# nes-programmer-1.net
KiCad netlist of a schematic drawn in EAGLE
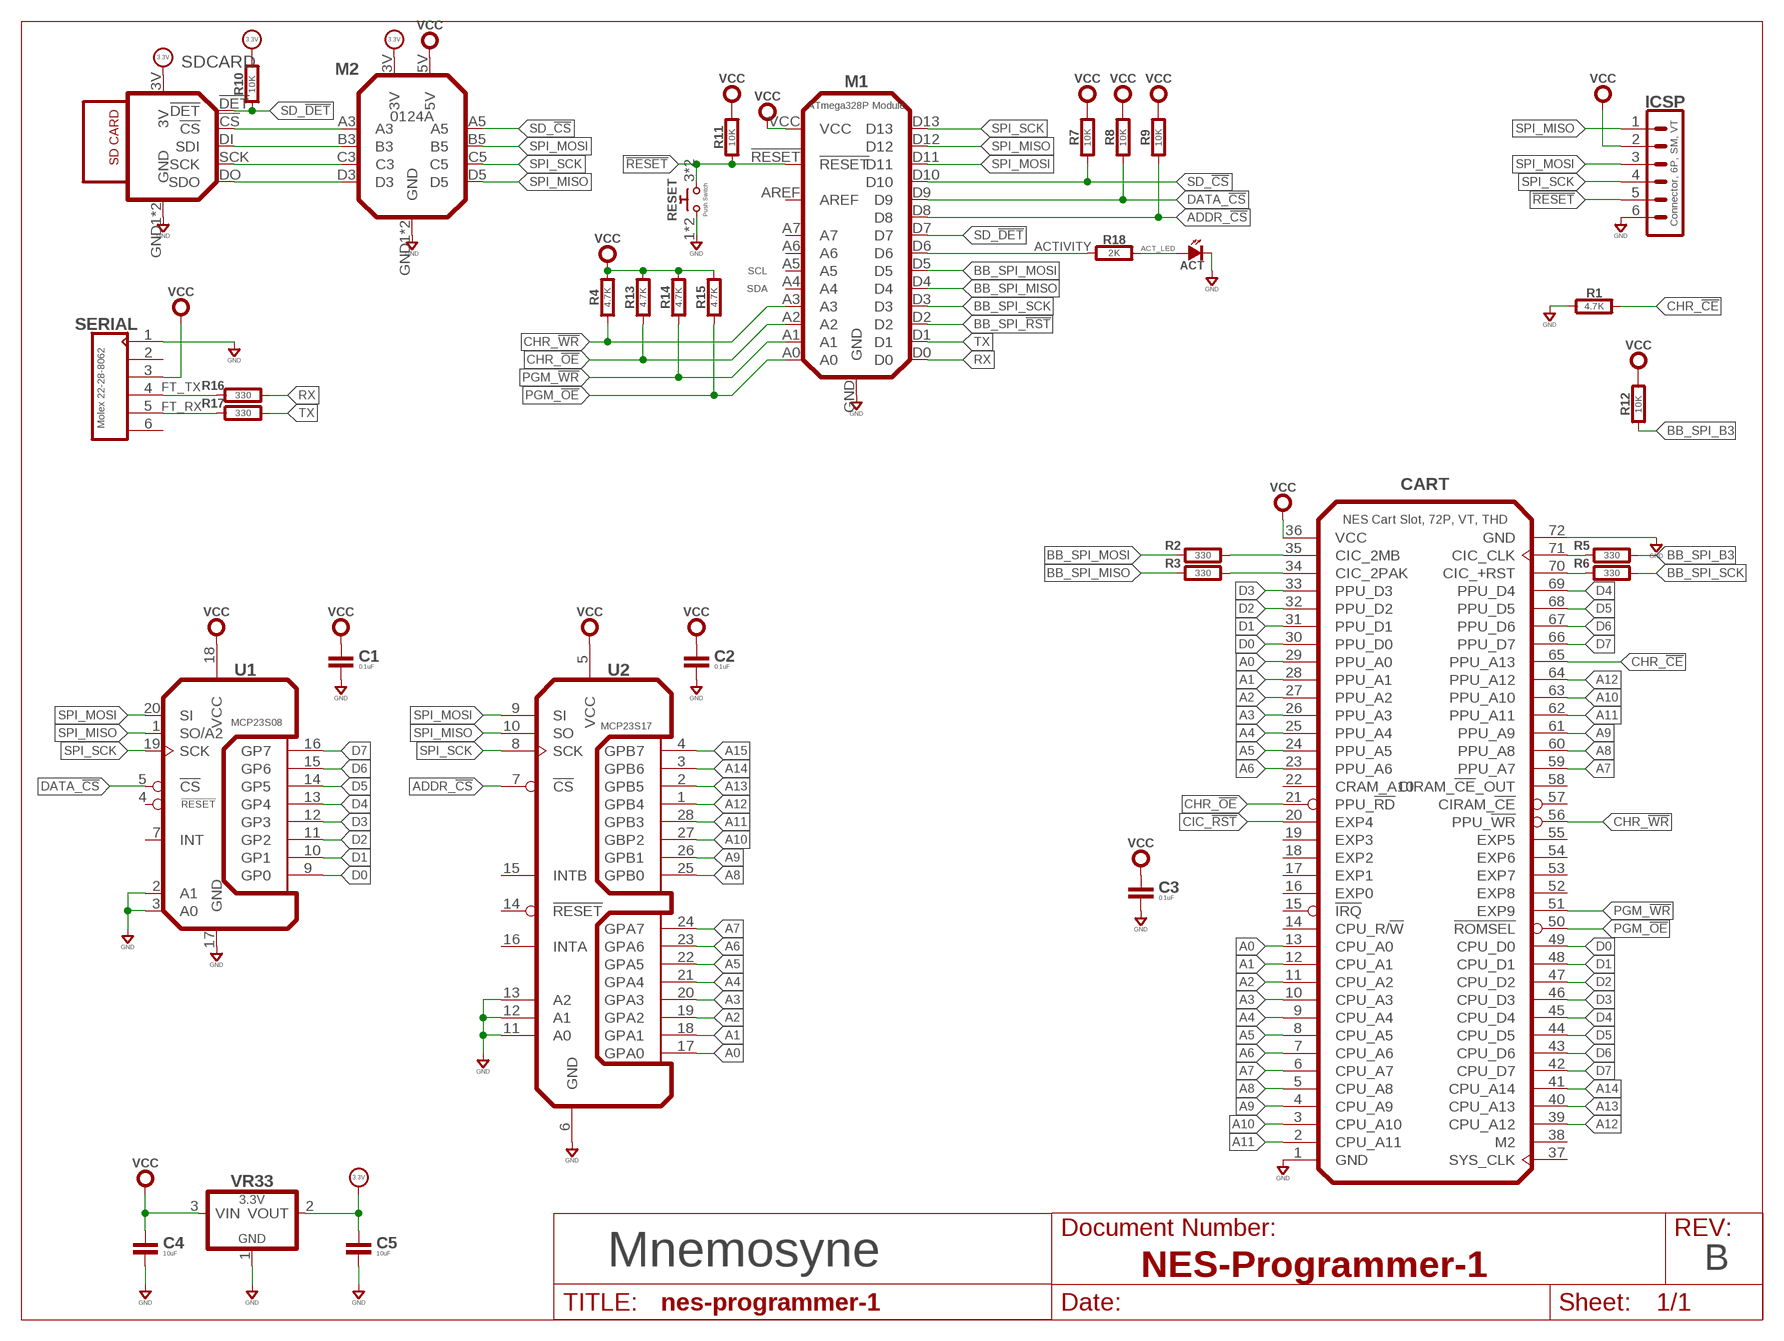
[diagram p0: schematic, sheet 1]

(export (version "E")
  (design (tool "Eeschema 10.0.6"))
  (components
    (comp (ref "ACT")
      (value "SMT0603")
      (footprint "eagle-import:SMD_0603")
      (libsource (lib "eagle-import") (part "SMT0603"))
    )
    (comp (ref "C1")
      (value "0.1uF")
      (footprint "eagle-import:0603-CAP")
      (libsource (lib "eagle-import") (part "CAPACITOR0603"))
    )
    (comp (ref "C2")
      (value "0.1uF")
      (footprint "eagle-import:0603-CAP")
      (libsource (lib "eagle-import") (part "CAPACITOR0603"))
    )
    (comp (ref "C3")
      (value "0.1uF")
      (footprint "eagle-import:0603-CAP")
      (libsource (lib "eagle-import") (part "CAPACITOR0603"))
    )
    (comp (ref "C4")
      (value "10uF")
      (footprint "eagle-import:0603-CAP")
      (libsource (lib "eagle-import") (part "CAPACITOR0603"))
    )
    (comp (ref "C5")
      (value "10uF")
      (footprint "eagle-import:0603-CAP")
      (libsource (lib "eagle-import") (part "CAPACITOR0603"))
    )
    (comp (ref "CART")
      (value "NES Cart Slot, 72P, VT, THD")
      (footprint "eagle-import:NES-CONNECTOR-VT-THD")
      (fields (field (name "MFR") "AliExpress") (field (name "MPN") "not defined"))
      (libsource (lib "eagle-import") (part "NES-RECEPTACLE-VT-THD"))
    )
    (comp (ref "ICSP")
      (value "Connector, 6P, SM, VT")
      (footprint "eagle-import:BM06B-SRSS-TB")
      (fields (field (name "MFR") "JST") (field (name "MPN") "BM06-SRSS-TB"))
      (libsource (lib "eagle-import") (part "06P-SM-VT-SMT"))
    )
    (comp (ref "M1")
      (value "ATmega328P Module")
      (footprint "eagle-import:0119A")
      (fields (field (name "MFR") "Circuit Monkey") (field (name "MPN") "0119A"))
      (libsource (lib "eagle-import") (part "0119REV-A"))
    )
    (comp (ref "M2")
      (value "0124A")
      (footprint "eagle-import:0124A")
      (fields (field (name "MFR") "Circuit Monkey"))
      (libsource (lib "eagle-import") (part "0124REV-A"))
    )
    (comp (ref "R1")
      (value "4.7K")
      (footprint "eagle-import:0603-RES")
      (libsource (lib "eagle-import") (part "RESISTOR0603"))
    )
    (comp (ref "R2")
      (value "330")
      (footprint "eagle-import:0603-RES")
      (libsource (lib "eagle-import") (part "RESISTOR0603"))
    )
    (comp (ref "R3")
      (value "330")
      (footprint "eagle-import:0603-RES")
      (libsource (lib "eagle-import") (part "RESISTOR0603"))
    )
    (comp (ref "R4")
      (value "4.7K")
      (footprint "eagle-import:0603-RES")
      (libsource (lib "eagle-import") (part "RESISTOR0603"))
    )
    (comp (ref "R5")
      (value "330")
      (footprint "eagle-import:0603-RES")
      (libsource (lib "eagle-import") (part "RESISTOR0603"))
    )
    (comp (ref "R6")
      (value "330")
      (footprint "eagle-import:0603-RES")
      (libsource (lib "eagle-import") (part "RESISTOR0603"))
    )
    (comp (ref "R7")
      (value "10K")
      (footprint "eagle-import:0603-RES")
      (libsource (lib "eagle-import") (part "RESISTOR0603"))
    )
    (comp (ref "R8")
      (value "10K")
      (footprint "eagle-import:0603-RES")
      (libsource (lib "eagle-import") (part "RESISTOR0603"))
    )
    (comp (ref "R9")
      (value "10K")
      (footprint "eagle-import:0603-RES")
      (libsource (lib "eagle-import") (part "RESISTOR0603"))
    )
    (comp (ref "R10")
      (value "10K")
      (footprint "eagle-import:0603-RES")
      (libsource (lib "eagle-import") (part "RESISTOR0603"))
    )
    (comp (ref "R11")
      (value "10K")
      (footprint "eagle-import:0603-RES")
      (libsource (lib "eagle-import") (part "RESISTOR0603"))
    )
    (comp (ref "R12")
      (value "10K")
      (footprint "eagle-import:0603-RES")
      (libsource (lib "eagle-import") (part "RESISTOR0603"))
    )
    (comp (ref "R13")
      (value "4.7K")
      (footprint "eagle-import:0603-RES")
      (libsource (lib "eagle-import") (part "RESISTOR0603"))
    )
    (comp (ref "R14")
      (value "4.7K")
      (footprint "eagle-import:0603-RES")
      (libsource (lib "eagle-import") (part "RESISTOR0603"))
    )
    (comp (ref "R15")
      (value "4.7K")
      (footprint "eagle-import:0603-RES")
      (libsource (lib "eagle-import") (part "RESISTOR0603"))
    )
    (comp (ref "R16")
      (value "330")
      (footprint "eagle-import:0603-RES")
      (libsource (lib "eagle-import") (part "RESISTOR0603"))
    )
    (comp (ref "R17")
      (value "330")
      (footprint "eagle-import:0603-RES")
      (libsource (lib "eagle-import") (part "RESISTOR0603"))
    )
    (comp (ref "R18")
      (value "2K")
      (footprint "eagle-import:0603-RES")
      (libsource (lib "eagle-import") (part "RESISTOR0603"))
    )
    (comp (ref "RESET")
      (value "Push Switch")
      (footprint "eagle-import:B3SN")
      (fields (field (name "MFR") "Omron") (field (name "MPN") "B3SN"))
      (libsource (lib "eagle-import") (part "PUSHBTN-MOMB3SN"))
    )
    (comp (ref "SDCARD")
      (value "0127REV-A")
      (footprint "eagle-import:0127A")
      (fields (field (name "MFR") "Circuit Monkey") (field (name "MPN") "0127"))
      (libsource (lib "eagle-import") (part "0127REV-A"))
    )
    (comp (ref "SERIAL")
      (value "Molex 22-28-8062")
      (footprint "eagle-import:MA06X1-RA-THD")
      (libsource (lib "eagle-import") (part "CON_06X1-RA"))
    )
    (comp (ref "U1")
      (value "MCP23S08")
      (footprint "eagle-import:QFN-20")
      (fields (field (name "MFR") "Microchip") (field (name "MPN") "MCP23S08-E/ML"))
      (libsource (lib "eagle-import") (part "MCP23S08-QFN"))
    )
    (comp (ref "U2")
      (value "MCP23S17")
      (footprint "eagle-import:QFN-28-6X6")
      (fields (field (name "MFR") "Microchip") (field (name "MPN") "MCP23S17-x/ML"))
      (libsource (lib "eagle-import") (part "MCP23S17-QFN"))
    )
    (comp (ref "VR33")
      (value "3.3V")
      (footprint "eagle-import:SOT-23")
      (fields (field (name "MPN") "AP2120N-3.3"))
      (libsource (lib "eagle-import") (part "LDO-3P--3.3V-SOT23"))
    )
  )
  (nets
    (net (code "1") (name "/ACTIVITY") (class "Default")
      (node (ref "M1") (pin "D6") (pinfunction "D6_D6") (pintype "bidirectional"))
      (node (ref "R18") (pin "1") (pinfunction "1_1") (pintype "passive"))
    )
    (net (code "2") (name "/ACT_LED") (class "Default")
      (node (ref "ACT") (pin "A") (pinfunction "A_A") (pintype "passive"))
      (node (ref "R18") (pin "2") (pinfunction "2_2") (pintype "passive"))
    )
    (net (code "3") (name "/ADDR_~{CS}") (class "Default")
      (node (ref "M1") (pin "D8") (pinfunction "D8_D8") (pintype "bidirectional"))
      (node (ref "R9") (pin "1") (pinfunction "1_1") (pintype "passive"))
      (node (ref "U2") (pin "7") (pinfunction "~{CS}_7") (pintype "input"))
    )
    (net (code "4") (name "/BB_SPI_~{RST}") (class "Default")
      (node (ref "M1") (pin "D2") (pinfunction "D2_D2") (pintype "bidirectional"))
    )
    (net (code "5") (name "/CHR_~{CE}") (class "Default")
      (node (ref "CART") (pin "65") (pinfunction "PPU_A13_65") (pintype "input"))
      (node (ref "R1") (pin "2") (pinfunction "2_2") (pintype "passive"))
    )
    (net (code "6") (name "/CHR_~{OE}") (class "Default")
      (node (ref "CART") (pin "21") (pinfunction "PPU_~{RD}_21") (pintype "input"))
      (node (ref "M1") (pin "A2") (pinfunction "A2_A2") (pintype "bidirectional"))
      (node (ref "R13") (pin "1") (pinfunction "1_1") (pintype "passive"))
    )
    (net (code "7") (name "/CHR_~{WR}") (class "Default")
      (node (ref "CART") (pin "56") (pinfunction "PPU_~{WR}_56") (pintype "input"))
      (node (ref "M1") (pin "A3") (pinfunction "A3_A3") (pintype "bidirectional"))
      (node (ref "R4") (pin "1") (pinfunction "1_1") (pintype "passive"))
    )
    (net (code "8") (name "/CIC_~{RST}") (class "Default")
      (node (ref "CART") (pin "20") (pinfunction "EXP4_20") (pintype "bidirectional"))
    )
    (net (code "9") (name "/DATA_~{CS}") (class "Default")
      (node (ref "M1") (pin "D9") (pinfunction "D9_D9") (pintype "bidirectional"))
      (node (ref "R8") (pin "1") (pinfunction "1_1") (pintype "passive"))
      (node (ref "U1") (pin "5") (pinfunction "~{CS}_5") (pintype "input"))
    )
    (net (code "10") (name "/FT_RX") (class "Default")
      (node (ref "R17") (pin "1") (pinfunction "1_1") (pintype "passive"))
      (node (ref "SERIAL") (pin "5") (pinfunction "5_5") (pintype "passive"))
    )
    (net (code "11") (name "/FT_TX") (class "Default")
      (node (ref "R16") (pin "1") (pinfunction "1_1") (pintype "passive"))
      (node (ref "SERIAL") (pin "4") (pinfunction "4_4") (pintype "passive"))
    )
    (net (code "12") (name "/PGM_~{OE}") (class "Default")
      (node (ref "CART") (pin "50") (pinfunction "~{ROMSEL}_50") (pintype "input"))
      (node (ref "M1") (pin "A0") (pinfunction "A0_A0") (pintype "bidirectional"))
      (node (ref "R15") (pin "1") (pinfunction "1_1") (pintype "passive"))
    )
    (net (code "13") (name "/PGM_~{WR}") (class "Default")
      (node (ref "CART") (pin "51") (pinfunction "EXP9_51") (pintype "bidirectional"))
      (node (ref "M1") (pin "A1") (pinfunction "A1_A1") (pintype "bidirectional"))
      (node (ref "R14") (pin "1") (pinfunction "1_1") (pintype "passive"))
    )
    (net (code "14") (name "/SD_~{CS}") (class "Default")
      (node (ref "M1") (pin "D10") (pinfunction "D10_D10") (pintype "bidirectional"))
      (node (ref "M2") (pin "A5") (pinfunction "A5_A5") (pintype "bidirectional"))
      (node (ref "R7") (pin "1") (pinfunction "1_1") (pintype "passive"))
    )
    (net (code "15") (name "/SD_~{DET}") (class "Default")
      (node (ref "M1") (pin "D7") (pinfunction "D7_D7") (pintype "bidirectional"))
      (node (ref "R10") (pin "1") (pinfunction "1_1") (pintype "passive"))
      (node (ref "SDCARD") (pin "!DET") (pinfunction "~{DET}_!DET") (pintype "bidirectional"))
    )
    (net (code "16") (name "/~{RESET}") (class "Default")
      (node (ref "ICSP") (pin "5") (pinfunction "5_5") (pintype "passive"))
      (node (ref "M1") (pin "!RESET") (pinfunction "~{RESET}_!RESET") (pintype "bidirectional"))
      (node (ref "R11") (pin "1") (pinfunction "1_1") (pintype "passive"))
      (node (ref "RESET") (pin "3") (pinfunction "2_3") (pintype "passive"))
      (node (ref "RESET") (pin "4") (pinfunction "2_4") (pintype "passive"))
    )
    (net (code "17") (name "3.3V") (class "Default")
      (node (ref "C5") (pin "1") (pinfunction "1_1") (pintype "passive"))
      (node (ref "M2") (pin "3V") (pinfunction "3V_3V") (pintype "bidirectional"))
      (node (ref "R10") (pin "2") (pinfunction "2_2") (pintype "passive"))
      (node (ref "SDCARD") (pin "3V") (pinfunction "3V_3V") (pintype "bidirectional"))
      (node (ref "VR33") (pin "2") (pinfunction "VOUT_2") (pintype "power_in"))
    )
    (net (code "18") (name "A0") (class "Default")
      (node (ref "CART") (pin "13") (pinfunction "CPU_A0_13") (pintype "input"))
      (node (ref "CART") (pin "29") (pinfunction "PPU_A0_29") (pintype "input"))
      (node (ref "U2") (pin "17") (pinfunction "GPA0_17") (pintype "bidirectional"))
    )
    (net (code "19") (name "A1") (class "Default")
      (node (ref "CART") (pin "12") (pinfunction "CPU_A1_12") (pintype "input"))
      (node (ref "CART") (pin "28") (pinfunction "PPU_A1_28") (pintype "input"))
      (node (ref "U2") (pin "18") (pinfunction "GPA1_18") (pintype "bidirectional"))
    )
    (net (code "20") (name "A2") (class "Default")
      (node (ref "CART") (pin "11") (pinfunction "CPU_A2_11") (pintype "input"))
      (node (ref "CART") (pin "27") (pinfunction "PPU_A2_27") (pintype "input"))
      (node (ref "U2") (pin "19") (pinfunction "GPA2_19") (pintype "bidirectional"))
    )
    (net (code "21") (name "A3") (class "Default")
      (node (ref "CART") (pin "10") (pinfunction "CPU_A3_10") (pintype "input"))
      (node (ref "CART") (pin "26") (pinfunction "PPU_A3_26") (pintype "input"))
      (node (ref "U2") (pin "20") (pinfunction "GPA3_20") (pintype "bidirectional"))
    )
    (net (code "22") (name "A4") (class "Default")
      (node (ref "CART") (pin "25") (pinfunction "PPU_A4_25") (pintype "input"))
      (node (ref "CART") (pin "9") (pinfunction "CPU_A4_9") (pintype "input"))
      (node (ref "U2") (pin "21") (pinfunction "GPA4_21") (pintype "bidirectional"))
    )
    (net (code "23") (name "A5") (class "Default")
      (node (ref "CART") (pin "24") (pinfunction "PPU_A5_24") (pintype "input"))
      (node (ref "CART") (pin "8") (pinfunction "CPU_A5_8") (pintype "input"))
      (node (ref "U2") (pin "22") (pinfunction "GPA5_22") (pintype "bidirectional"))
    )
    (net (code "24") (name "A6") (class "Default")
      (node (ref "CART") (pin "23") (pinfunction "PPU_A6_23") (pintype "input"))
      (node (ref "CART") (pin "7") (pinfunction "CPU_A6_7") (pintype "input"))
      (node (ref "U2") (pin "23") (pinfunction "GPA6_23") (pintype "bidirectional"))
    )
    (net (code "25") (name "A7") (class "Default")
      (node (ref "CART") (pin "59") (pinfunction "PPU_A7_59") (pintype "input"))
      (node (ref "CART") (pin "6") (pinfunction "CPU_A7_6") (pintype "input"))
      (node (ref "U2") (pin "24") (pinfunction "GPA7_24") (pintype "bidirectional"))
    )
    (net (code "26") (name "A8") (class "Default")
      (node (ref "CART") (pin "5") (pinfunction "CPU_A8_5") (pintype "input"))
      (node (ref "CART") (pin "60") (pinfunction "PPU_A8_60") (pintype "input"))
      (node (ref "U2") (pin "25") (pinfunction "GPB0_25") (pintype "bidirectional"))
    )
    (net (code "27") (name "A9") (class "Default")
      (node (ref "CART") (pin "4") (pinfunction "CPU_A9_4") (pintype "input"))
      (node (ref "CART") (pin "61") (pinfunction "PPU_A9_61") (pintype "input"))
      (node (ref "U2") (pin "26") (pinfunction "GPB1_26") (pintype "bidirectional"))
    )
    (net (code "28") (name "A10") (class "Default")
      (node (ref "CART") (pin "3") (pinfunction "CPU_A10_3") (pintype "input"))
      (node (ref "CART") (pin "63") (pinfunction "PPU_A10_63") (pintype "input"))
      (node (ref "U2") (pin "27") (pinfunction "GBP2_27") (pintype "bidirectional"))
    )
    (net (code "29") (name "A11") (class "Default")
      (node (ref "CART") (pin "2") (pinfunction "CPU_A11_2") (pintype "input"))
      (node (ref "CART") (pin "62") (pinfunction "PPU_A11_62") (pintype "input"))
      (node (ref "U2") (pin "28") (pinfunction "GPB3_28") (pintype "bidirectional"))
    )
    (net (code "30") (name "A12") (class "Default")
      (node (ref "CART") (pin "39") (pinfunction "CPU_A12_39") (pintype "input"))
      (node (ref "CART") (pin "64") (pinfunction "PPU_A12_64") (pintype "input"))
      (node (ref "U2") (pin "1") (pinfunction "GPB4_1") (pintype "bidirectional"))
    )
    (net (code "31") (name "A13") (class "Default")
      (node (ref "CART") (pin "40") (pinfunction "CPU_A13_40") (pintype "input"))
      (node (ref "U2") (pin "2") (pinfunction "GPB5_2") (pintype "bidirectional"))
    )
    (net (code "32") (name "A14") (class "Default")
      (node (ref "CART") (pin "41") (pinfunction "CPU_A14_41") (pintype "input"))
      (node (ref "U2") (pin "3") (pinfunction "GPB6_3") (pintype "bidirectional"))
    )
    (net (code "33") (name "A15") (class "Default")
      (node (ref "U2") (pin "4") (pinfunction "GPB7_4") (pintype "bidirectional"))
    )
    (net (code "34") (name "BB_SPI_B3") (class "Default")
      (node (ref "R12") (pin "1") (pinfunction "1_1") (pintype "passive"))
      (node (ref "R5") (pin "2") (pinfunction "2_2") (pintype "passive"))
    )
    (net (code "35") (name "BB_SPI_MISO") (class "Default")
      (node (ref "M1") (pin "D4") (pinfunction "D4_D4") (pintype "bidirectional"))
      (node (ref "R3") (pin "1") (pinfunction "1_1") (pintype "passive"))
    )
    (net (code "36") (name "BB_SPI_MOSI") (class "Default")
      (node (ref "M1") (pin "D5") (pinfunction "D5_D5") (pintype "bidirectional"))
      (node (ref "R2") (pin "1") (pinfunction "1_1") (pintype "passive"))
    )
    (net (code "37") (name "BB_SPI_SCK") (class "Default")
      (node (ref "M1") (pin "D3") (pinfunction "D3_D3") (pintype "bidirectional"))
      (node (ref "R6") (pin "2") (pinfunction "2_2") (pintype "passive"))
    )
    (net (code "38") (name "D0") (class "Default")
      (node (ref "CART") (pin "30") (pinfunction "PPU_D0_30") (pintype "bidirectional"))
      (node (ref "CART") (pin "49") (pinfunction "CPU_D0_49") (pintype "bidirectional"))
      (node (ref "U1") (pin "9") (pinfunction "GP0_9") (pintype "bidirectional"))
    )
    (net (code "39") (name "D1") (class "Default")
      (node (ref "CART") (pin "31") (pinfunction "PPU_D1_31") (pintype "bidirectional"))
      (node (ref "CART") (pin "48") (pinfunction "CPU_D1_48") (pintype "bidirectional"))
      (node (ref "U1") (pin "10") (pinfunction "GP1_10") (pintype "bidirectional"))
    )
    (net (code "40") (name "D2") (class "Default")
      (node (ref "CART") (pin "32") (pinfunction "PPU_D2_32") (pintype "bidirectional"))
      (node (ref "CART") (pin "47") (pinfunction "CPU_D2_47") (pintype "bidirectional"))
      (node (ref "U1") (pin "11") (pinfunction "GP2_11") (pintype "bidirectional"))
    )
    (net (code "41") (name "D3") (class "Default")
      (node (ref "CART") (pin "33") (pinfunction "PPU_D3_33") (pintype "bidirectional"))
      (node (ref "CART") (pin "46") (pinfunction "CPU_D3_46") (pintype "bidirectional"))
      (node (ref "U1") (pin "12") (pinfunction "GP3_12") (pintype "bidirectional"))
    )
    (net (code "42") (name "D4") (class "Default")
      (node (ref "CART") (pin "45") (pinfunction "CPU_D4_45") (pintype "bidirectional"))
      (node (ref "CART") (pin "69") (pinfunction "PPU_D4_69") (pintype "bidirectional"))
      (node (ref "U1") (pin "13") (pinfunction "GP4_13") (pintype "bidirectional"))
    )
    (net (code "43") (name "D5") (class "Default")
      (node (ref "CART") (pin "44") (pinfunction "CPU_D5_44") (pintype "bidirectional"))
      (node (ref "CART") (pin "68") (pinfunction "PPU_D5_68") (pintype "bidirectional"))
      (node (ref "U1") (pin "14") (pinfunction "GP5_14") (pintype "bidirectional"))
    )
    (net (code "44") (name "D6") (class "Default")
      (node (ref "CART") (pin "43") (pinfunction "CPU_D6_43") (pintype "bidirectional"))
      (node (ref "CART") (pin "67") (pinfunction "PPU_D6_67") (pintype "bidirectional"))
      (node (ref "U1") (pin "15") (pinfunction "GP6_15") (pintype "bidirectional"))
    )
    (net (code "45") (name "D7") (class "Default")
      (node (ref "CART") (pin "42") (pinfunction "CPU_D7_42") (pintype "bidirectional"))
      (node (ref "CART") (pin "66") (pinfunction "PPU_D7_66") (pintype "bidirectional"))
      (node (ref "U1") (pin "16") (pinfunction "GP7_16") (pintype "bidirectional"))
    )
    (net (code "46") (name "GND") (class "Default")
      (node (ref "ACT") (pin "K") (pinfunction "C_K") (pintype "passive"))
      (node (ref "C1") (pin "2") (pinfunction "2_2") (pintype "passive"))
      (node (ref "C2") (pin "2") (pinfunction "2_2") (pintype "passive"))
      (node (ref "C3") (pin "2") (pinfunction "2_2") (pintype "passive"))
      (node (ref "C4") (pin "2") (pinfunction "2_2") (pintype "passive"))
      (node (ref "C5") (pin "2") (pinfunction "2_2") (pintype "passive"))
      (node (ref "CART") (pin "1") (pinfunction "GND_1") (pintype "power_in"))
      (node (ref "CART") (pin "72") (pinfunction "GND_72") (pintype "bidirectional"))
      (node (ref "ICSP") (pin "6") (pinfunction "6_6") (pintype "passive"))
      (node (ref "M1") (pin "GND") (pinfunction "GND_GND") (pintype "bidirectional"))
      (node (ref "M2") (pin "GND1") (pinfunction "GND_GND1") (pintype "bidirectional"))
      (node (ref "M2") (pin "GND2") (pinfunction "GND_GND2") (pintype "bidirectional"))
      (node (ref "R1") (pin "1") (pinfunction "1_1") (pintype "passive"))
      (node (ref "RESET") (pin "1") (pinfunction "1_1") (pintype "passive"))
      (node (ref "RESET") (pin "2") (pinfunction "1_2") (pintype "passive"))
      (node (ref "SDCARD") (pin "GND1") (pinfunction "GND_GND1") (pintype "bidirectional"))
      (node (ref "SDCARD") (pin "GND2") (pinfunction "GND_GND2") (pintype "bidirectional"))
      (node (ref "SERIAL") (pin "1") (pinfunction "1_1") (pintype "passive"))
      (node (ref "U1") (pin "17") (pinfunction "GND_17") (pintype "power_in"))
      (node (ref "U1") (pin "2") (pinfunction "A1_2") (pintype "input"))
      (node (ref "U1") (pin "3") (pinfunction "A0_3") (pintype "input"))
      (node (ref "U2") (pin "11") (pinfunction "A0_11") (pintype "input"))
      (node (ref "U2") (pin "12") (pinfunction "A1_12") (pintype "input"))
      (node (ref "U2") (pin "13") (pinfunction "A2_13") (pintype "input"))
      (node (ref "U2") (pin "6") (pinfunction "GND_6") (pintype "power_in"))
      (node (ref "VR33") (pin "1") (pinfunction "GND_1") (pintype "power_in"))
    )
    (net (code "47") (name "Net-(CART-CIC_+RST)") (class "Default")
      (node (ref "CART") (pin "70") (pinfunction "CIC_+RST_70") (pintype "input"))
      (node (ref "R6") (pin "1") (pinfunction "1_1") (pintype "passive"))
    )
    (net (code "48") (name "Net-(CART-CIC_2MB)") (class "Default")
      (node (ref "CART") (pin "35") (pinfunction "CIC_2MB_35") (pintype "output"))
      (node (ref "R2") (pin "2") (pinfunction "2_2") (pintype "passive"))
    )
    (net (code "49") (name "Net-(CART-CIC_2PAK)") (class "Default")
      (node (ref "CART") (pin "34") (pinfunction "CIC_2PAK_34") (pintype "input"))
      (node (ref "R3") (pin "2") (pinfunction "2_2") (pintype "passive"))
    )
    (net (code "50") (name "Net-(CART-CIC_CLK)") (class "Default")
      (node (ref "CART") (pin "71") (pinfunction "CIC_CLK_71") (pintype "input"))
      (node (ref "R5") (pin "1") (pinfunction "1_1") (pintype "passive"))
    )
    (net (code "51") (name "Net-(M2-PadC3)") (class "Default")
      (node (ref "M2") (pin "C3") (pinfunction "C3_C3") (pintype "bidirectional"))
      (node (ref "SDCARD") (pin "SCK") (pinfunction "SCK_SCK") (pintype "bidirectional"))
    )
    (net (code "52") (name "Net-(SDCARD-SDI)") (class "Default")
      (node (ref "M2") (pin "B3") (pinfunction "B3_B3") (pintype "bidirectional"))
      (node (ref "SDCARD") (pin "DI") (pinfunction "SDI_DI") (pintype "bidirectional"))
    )
    (net (code "53") (name "Net-(SDCARD-SDO)") (class "Default")
      (node (ref "M2") (pin "D3") (pinfunction "D3_D3") (pintype "bidirectional"))
      (node (ref "SDCARD") (pin "DO") (pinfunction "SDO_DO") (pintype "bidirectional"))
    )
    (net (code "54") (name "Net-(SDCARD-~{CS})") (class "Default")
      (node (ref "M2") (pin "A3") (pinfunction "A3_A3") (pintype "bidirectional"))
      (node (ref "SDCARD") (pin "!CS") (pinfunction "~{CS}_!CS") (pintype "bidirectional"))
    )
    (net (code "55") (name "RX") (class "Default")
      (node (ref "M1") (pin "D0") (pinfunction "D0_D0") (pintype "bidirectional"))
      (node (ref "R16") (pin "2") (pinfunction "2_2") (pintype "passive"))
    )
    (net (code "56") (name "SPI_MISO") (class "Default")
      (node (ref "ICSP") (pin "1") (pinfunction "1_1") (pintype "passive"))
      (node (ref "M1") (pin "D12") (pinfunction "D12_D12") (pintype "bidirectional"))
      (node (ref "M2") (pin "D5") (pinfunction "D5_D5") (pintype "bidirectional"))
      (node (ref "U1") (pin "1") (pinfunction "SO/A2_1") (pintype "input"))
      (node (ref "U2") (pin "10") (pinfunction "SO_10") (pintype "output"))
    )
    (net (code "57") (name "SPI_MOSI") (class "Default")
      (node (ref "ICSP") (pin "3") (pinfunction "3_3") (pintype "passive"))
      (node (ref "M1") (pin "D11") (pinfunction "D11_D11") (pintype "bidirectional"))
      (node (ref "M2") (pin "B5") (pinfunction "B5_B5") (pintype "bidirectional"))
      (node (ref "U1") (pin "20") (pinfunction "SI_20") (pintype "input"))
      (node (ref "U2") (pin "9") (pinfunction "SI_9") (pintype "input"))
    )
    (net (code "58") (name "SPI_SCK") (class "Default")
      (node (ref "ICSP") (pin "4") (pinfunction "4_4") (pintype "passive"))
      (node (ref "M1") (pin "D13") (pinfunction "D13_D13") (pintype "bidirectional"))
      (node (ref "M2") (pin "C5") (pinfunction "C5_C5") (pintype "bidirectional"))
      (node (ref "U1") (pin "19") (pinfunction "SCK_19") (pintype "input"))
      (node (ref "U2") (pin "8") (pinfunction "SCK_8") (pintype "input"))
    )
    (net (code "59") (name "TX") (class "Default")
      (node (ref "M1") (pin "D1") (pinfunction "D1_D1") (pintype "bidirectional"))
      (node (ref "R17") (pin "2") (pinfunction "2_2") (pintype "passive"))
    )
    (net (code "60") (name "VCC") (class "Default")
      (node (ref "C1") (pin "1") (pinfunction "1_1") (pintype "passive"))
      (node (ref "C2") (pin "1") (pinfunction "1_1") (pintype "passive"))
      (node (ref "C3") (pin "1") (pinfunction "1_1") (pintype "passive"))
      (node (ref "C4") (pin "1") (pinfunction "1_1") (pintype "passive"))
      (node (ref "CART") (pin "36") (pinfunction "VCC_36") (pintype "power_in"))
      (node (ref "ICSP") (pin "2") (pinfunction "2_2") (pintype "passive"))
      (node (ref "M1") (pin "VCC") (pinfunction "VCC_VCC") (pintype "bidirectional"))
      (node (ref "M2") (pin "5V") (pinfunction "5V_5V") (pintype "bidirectional"))
      (node (ref "R11") (pin "2") (pinfunction "2_2") (pintype "passive"))
      (node (ref "R12") (pin "2") (pinfunction "2_2") (pintype "passive"))
      (node (ref "R13") (pin "2") (pinfunction "2_2") (pintype "passive"))
      (node (ref "R14") (pin "2") (pinfunction "2_2") (pintype "passive"))
      (node (ref "R15") (pin "2") (pinfunction "2_2") (pintype "passive"))
      (node (ref "R4") (pin "2") (pinfunction "2_2") (pintype "passive"))
      (node (ref "R7") (pin "2") (pinfunction "2_2") (pintype "passive"))
      (node (ref "R8") (pin "2") (pinfunction "2_2") (pintype "passive"))
      (node (ref "R9") (pin "2") (pinfunction "2_2") (pintype "passive"))
      (node (ref "SERIAL") (pin "3") (pinfunction "3_3") (pintype "passive"))
      (node (ref "U1") (pin "18") (pinfunction "VCC_18") (pintype "power_in"))
      (node (ref "U2") (pin "5") (pinfunction "VCC_5") (pintype "power_in"))
      (node (ref "VR33") (pin "3") (pinfunction "VIN_3") (pintype "power_in"))
    )
    (net (code "61") (name "unconnected-(CART-CIRAM_~{CE}-Pad57)") (class "Default")
      (node (ref "CART") (pin "57") (pinfunction "CIRAM_~{CE}_57") (pintype "output"))
    )
    (net (code "62") (name "unconnected-(CART-CIRAM_~{CE}_OUT-Pad58)") (class "Default")
      (node (ref "CART") (pin "58") (pinfunction "CIRAM_~{CE}_OUT_58") (pintype "input"))
    )
    (net (code "63") (name "unconnected-(CART-CPU_R{slash}~{W}-Pad14)") (class "Default")
      (node (ref "CART") (pin "14") (pinfunction "CPU_R/~{W}_14") (pintype "input"))
    )
    (net (code "64") (name "unconnected-(CART-CRAM_A10-Pad22)") (class "Default")
      (node (ref "CART") (pin "22") (pinfunction "CRAM_A10_22") (pintype "input"))
    )
    (net (code "65") (name "unconnected-(CART-EXP0-Pad16)") (class "Default")
      (node (ref "CART") (pin "16") (pinfunction "EXP0_16") (pintype "bidirectional"))
    )
    (net (code "66") (name "unconnected-(CART-EXP1-Pad17)") (class "Default")
      (node (ref "CART") (pin "17") (pinfunction "EXP1_17") (pintype "bidirectional"))
    )
    (net (code "67") (name "unconnected-(CART-EXP2-Pad18)") (class "Default")
      (node (ref "CART") (pin "18") (pinfunction "EXP2_18") (pintype "bidirectional"))
    )
    (net (code "68") (name "unconnected-(CART-EXP3-Pad19)") (class "Default")
      (node (ref "CART") (pin "19") (pinfunction "EXP3_19") (pintype "bidirectional"))
    )
    (net (code "69") (name "unconnected-(CART-EXP5-Pad55)") (class "Default")
      (node (ref "CART") (pin "55") (pinfunction "EXP5_55") (pintype "bidirectional"))
    )
    (net (code "70") (name "unconnected-(CART-EXP6-Pad54)") (class "Default")
      (node (ref "CART") (pin "54") (pinfunction "EXP6_54") (pintype "bidirectional"))
    )
    (net (code "71") (name "unconnected-(CART-EXP7-Pad53)") (class "Default")
      (node (ref "CART") (pin "53") (pinfunction "EXP7_53") (pintype "bidirectional"))
    )
    (net (code "72") (name "unconnected-(CART-EXP8-Pad52)") (class "Default")
      (node (ref "CART") (pin "52") (pinfunction "EXP8_52") (pintype "bidirectional"))
    )
    (net (code "73") (name "unconnected-(CART-M2-Pad38)") (class "Default")
      (node (ref "CART") (pin "38") (pinfunction "M2_38") (pintype "input"))
    )
    (net (code "74") (name "unconnected-(CART-SYS_CLK-Pad37)") (class "Default")
      (node (ref "CART") (pin "37") (pinfunction "SYS_CLK_37") (pintype "input"))
    )
    (net (code "75") (name "unconnected-(CART-~{IRQ}-Pad15)") (class "Default")
      (node (ref "CART") (pin "15") (pinfunction "~{IRQ}_15") (pintype "output"))
    )
    (net (code "76") (name "unconnected-(M1-PadA4)") (class "Default")
      (node (ref "M1") (pin "A4") (pinfunction "A4_A4") (pintype "bidirectional"))
    )
    (net (code "77") (name "unconnected-(M1-PadA5)") (class "Default")
      (node (ref "M1") (pin "A5") (pinfunction "A5_A5") (pintype "bidirectional"))
    )
    (net (code "78") (name "unconnected-(M1-PadA6)") (class "Default")
      (node (ref "M1") (pin "A6") (pinfunction "A6_A6") (pintype "bidirectional"))
    )
    (net (code "79") (name "unconnected-(M1-PadA7)") (class "Default")
      (node (ref "M1") (pin "A7") (pinfunction "A7_A7") (pintype "bidirectional"))
    )
    (net (code "80") (name "unconnected-(M1-PadAREF)") (class "Default")
      (node (ref "M1") (pin "AREF") (pinfunction "AREF_AREF") (pintype "bidirectional"))
    )
    (net (code "81") (name "unconnected-(SERIAL-Pad2)") (class "Default")
      (node (ref "SERIAL") (pin "2") (pinfunction "2_2") (pintype "passive"))
    )
    (net (code "82") (name "unconnected-(SERIAL-Pad6)") (class "Default")
      (node (ref "SERIAL") (pin "6") (pinfunction "6_6") (pintype "passive"))
    )
    (net (code "83") (name "unconnected-(U1-INT-Pad7)") (class "Default")
      (node (ref "U1") (pin "7") (pinfunction "INT_7") (pintype "output"))
    )
    (net (code "84") (name "unconnected-(U1-~{RESET}-Pad4)") (class "Default")
      (node (ref "U1") (pin "4") (pinfunction "~{RESET}_4") (pintype "input"))
    )
    (net (code "85") (name "unconnected-(U2-INTA-Pad16)") (class "Default")
      (node (ref "U2") (pin "16") (pinfunction "INTA_16") (pintype "output"))
    )
    (net (code "86") (name "unconnected-(U2-INTB-Pad15)") (class "Default")
      (node (ref "U2") (pin "15") (pinfunction "INTB_15") (pintype "output"))
    )
    (net (code "87") (name "unconnected-(U2-~{RESET}-Pad14)") (class "Default")
      (node (ref "U2") (pin "14") (pinfunction "~{RESET}_14") (pintype "input"))
    )
  )
)
